# imu_69.net
KiCad netlist of a schematic drawn in EAGLE
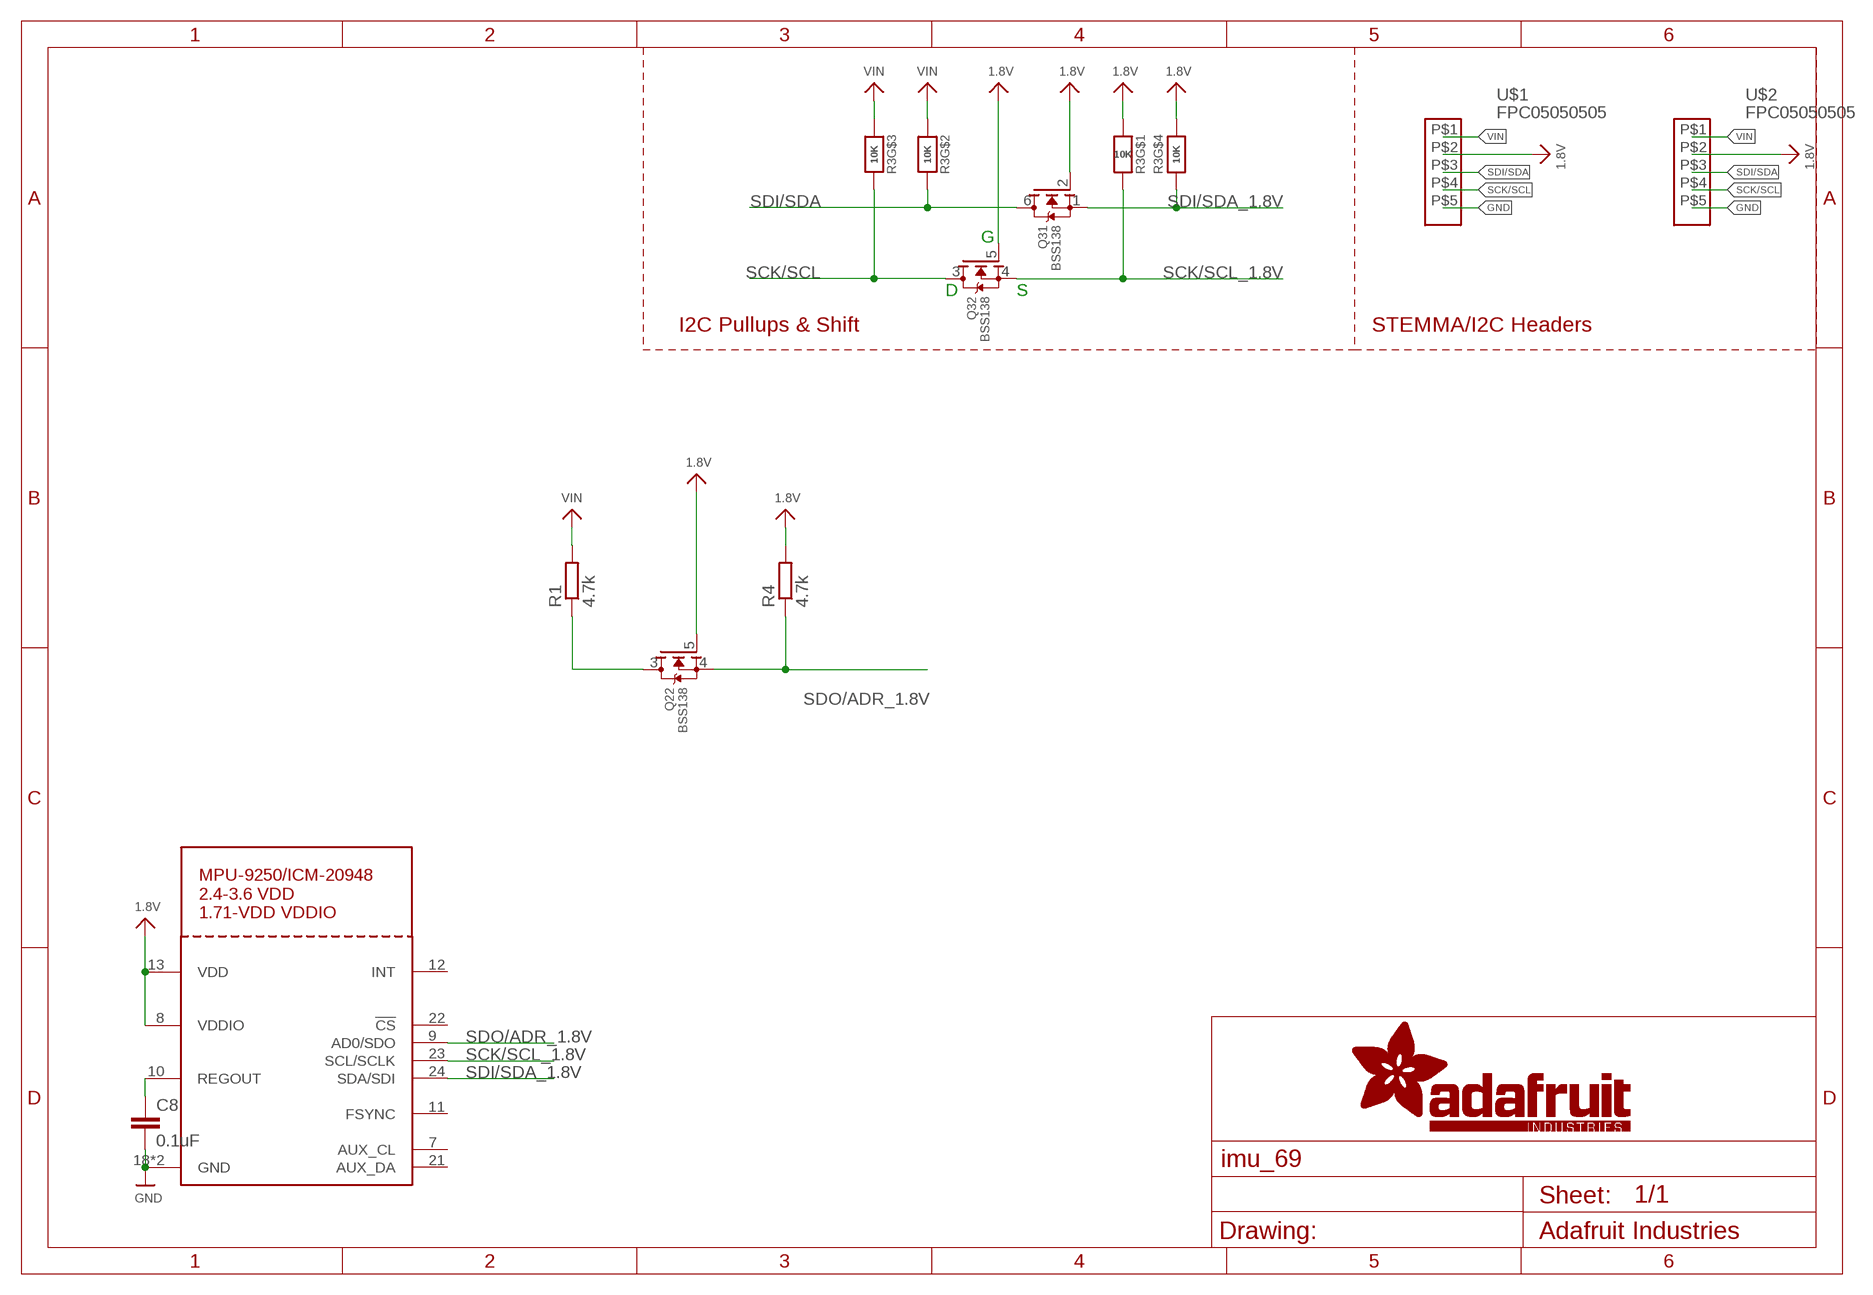
[diagram p0: schematic, sheet 1]

(export (version "E")
  (design (tool "Eeschema 10.0.6"))
  (components
    (comp (ref "C8")
      (value "0.1uF")
      (footprint "eagle-import:C0201")
      (libsource (lib "eagle-import") (part "C-EUC0201"))
    )
    (comp (ref "Q2")
      (value "BSS138")
      (footprint "eagle-import:SOT363")
      (libsource (lib "eagle-import") (part "MOSFET-N_DUAL"))
    )
    (comp (ref "Q3")
      (value "BSS138")
      (footprint "eagle-import:SOT363")
      (libsource (lib "eagle-import") (part "MOSFET-N_DUAL"))
    )
    (comp (ref "R1")
      (value "4.7k")
      (footprint "eagle-import:R0402")
      (libsource (lib "eagle-import") (part "R-EU_R0402"))
    )
    (comp (ref "R3")
      (value "10K")
      (footprint "eagle-import:RESPACK_4X0603")
      (libsource (lib "eagle-import") (part "RESISTOR_4PACK"))
    )
    (comp (ref "R4")
      (value "4.7k")
      (footprint "eagle-import:R0402")
      (libsource (lib "eagle-import") (part "R-EU_R0402"))
    )
    (comp (ref "U$1")
      (value "FPC05050505")
      (footprint "eagle-import:FPB0505")
      (libsource (lib "eagle-import") (part "FPC05050505"))
    )
    (comp (ref "U$2")
      (value "FPC05050505")
      (footprint "eagle-import:FPB0505")
      (libsource (lib "eagle-import") (part "FPC05050505"))
    )
    (comp (ref "U$21")
      (value "MPU-9250_ICM20948")
      (footprint "eagle-import:QFN24_3MM_NOEP")
      (libsource (lib "eagle-import") (part "MPU-9250_ICM20948"))
    )
  )
  (nets
    (net (code "1") (name "/SCK{slash}SCL_1.8V") (class "Default")
      (node (ref "Q3") (pin "4") (pinfunction "S_4") (pintype "bidirectional"))
      (node (ref "R3") (pin "1") (pinfunction "1_1") (pintype "passive"))
      (node (ref "U$21") (pin "23") (pinfunction "SCL/SCLK_23") (pintype "bidirectional"))
    )
    (net (code "2") (name "/SDI{slash}SDA_1.8V") (class "Default")
      (node (ref "Q3") (pin "1") (pinfunction "S_1") (pintype "bidirectional"))
      (node (ref "R3") (pin "5") (pinfunction "2_5") (pintype "passive"))
      (node (ref "U$21") (pin "24") (pinfunction "SDA/SDI_24") (pintype "bidirectional"))
    )
    (net (code "3") (name "/SDO{slash}ADR_1.8V") (class "Default")
      (node (ref "Q2") (pin "4") (pinfunction "S_4") (pintype "bidirectional"))
      (node (ref "R4") (pin "1") (pinfunction "1_1") (pintype "passive"))
      (node (ref "U$21") (pin "9") (pinfunction "AD0/SDO_9") (pintype "bidirectional"))
    )
    (net (code "4") (name "1.8V") (class "Default")
      (node (ref "Q2") (pin "5") (pinfunction "G_5") (pintype "bidirectional"))
      (node (ref "Q3") (pin "2") (pinfunction "G_2") (pintype "bidirectional"))
      (node (ref "Q3") (pin "5") (pinfunction "G_5") (pintype "bidirectional"))
      (node (ref "R3") (pin "4") (pinfunction "1_4") (pintype "passive"))
      (node (ref "R3") (pin "8") (pinfunction "2_8") (pintype "passive"))
      (node (ref "R4") (pin "2") (pinfunction "2_2") (pintype "passive"))
      (node (ref "U$1") (pin "P$2") (pinfunction "P$2_P$2") (pintype "bidirectional"))
      (node (ref "U$2") (pin "P$2") (pinfunction "P$2_P$2") (pintype "bidirectional"))
      (node (ref "U$21") (pin "13") (pinfunction "VDD_13") (pintype "bidirectional"))
      (node (ref "U$21") (pin "8") (pinfunction "VDDIO_8") (pintype "bidirectional"))
    )
    (net (code "5") (name "GND") (class "Default")
      (node (ref "C8") (pin "2") (pinfunction "2_2") (pintype "passive"))
      (node (ref "U$1") (pin "P$5") (pinfunction "P$5_P$5") (pintype "bidirectional"))
      (node (ref "U$2") (pin "P$5") (pinfunction "P$5_P$5") (pintype "bidirectional"))
      (node (ref "U$21") (pin "18") (pinfunction "GND_18") (pintype "bidirectional"))
      (node (ref "U$21") (pin "20") (pinfunction "GND_20") (pintype "bidirectional"))
    )
    (net (code "6") (name "Net-(Q2B-D)") (class "Default")
      (node (ref "Q2") (pin "3") (pinfunction "D_3") (pintype "bidirectional"))
      (node (ref "R1") (pin "1") (pinfunction "1_1") (pintype "passive"))
    )
    (net (code "7") (name "Net-(U$21-REGOUT)") (class "Default")
      (node (ref "C8") (pin "1") (pinfunction "1_1") (pintype "passive"))
      (node (ref "U$21") (pin "10") (pinfunction "REGOUT_10") (pintype "bidirectional"))
    )
    (net (code "8") (name "SCK{slash}SCL") (class "Default")
      (node (ref "Q3") (pin "3") (pinfunction "D_3") (pintype "bidirectional"))
      (node (ref "R3") (pin "6") (pinfunction "2_6") (pintype "passive"))
      (node (ref "U$1") (pin "P$4") (pinfunction "P$4_P$4") (pintype "bidirectional"))
      (node (ref "U$2") (pin "P$4") (pinfunction "P$4_P$4") (pintype "bidirectional"))
    )
    (net (code "9") (name "SDI{slash}SDA") (class "Default")
      (node (ref "Q3") (pin "6") (pinfunction "D_6") (pintype "bidirectional"))
      (node (ref "R3") (pin "7") (pinfunction "2_7") (pintype "passive"))
      (node (ref "U$1") (pin "P$3") (pinfunction "P$3_P$3") (pintype "bidirectional"))
      (node (ref "U$2") (pin "P$3") (pinfunction "P$3_P$3") (pintype "bidirectional"))
    )
    (net (code "10") (name "VIN") (class "Default")
      (node (ref "R1") (pin "2") (pinfunction "2_2") (pintype "passive"))
      (node (ref "R3") (pin "2") (pinfunction "1_2") (pintype "passive"))
      (node (ref "R3") (pin "3") (pinfunction "1_3") (pintype "passive"))
      (node (ref "U$1") (pin "P$1") (pinfunction "P$1_P$1") (pintype "bidirectional"))
      (node (ref "U$2") (pin "P$1") (pinfunction "P$1_P$1") (pintype "bidirectional"))
    )
    (net (code "11") (name "unconnected-(U$21-AUX_CL-Pad7)") (class "Default")
      (node (ref "U$21") (pin "7") (pinfunction "AUX_CL_7") (pintype "bidirectional"))
    )
    (net (code "12") (name "unconnected-(U$21-AUX_DA-Pad21)") (class "Default")
      (node (ref "U$21") (pin "21") (pinfunction "AUX_DA_21") (pintype "bidirectional"))
    )
    (net (code "13") (name "unconnected-(U$21-FSYNC-Pad11)") (class "Default")
      (node (ref "U$21") (pin "11") (pinfunction "FSYNC_11") (pintype "bidirectional"))
    )
    (net (code "14") (name "unconnected-(U$21-INT-Pad12)") (class "Default")
      (node (ref "U$21") (pin "12") (pinfunction "INT_12") (pintype "bidirectional"))
    )
    (net (code "15") (name "unconnected-(U$21-~{CS}-Pad22)") (class "Default")
      (node (ref "U$21") (pin "22") (pinfunction "~{CS}_22") (pintype "bidirectional"))
    )
  )
)
